# Display_SACA.net
KiCad netlist of a schematic drawn in Altium Designer
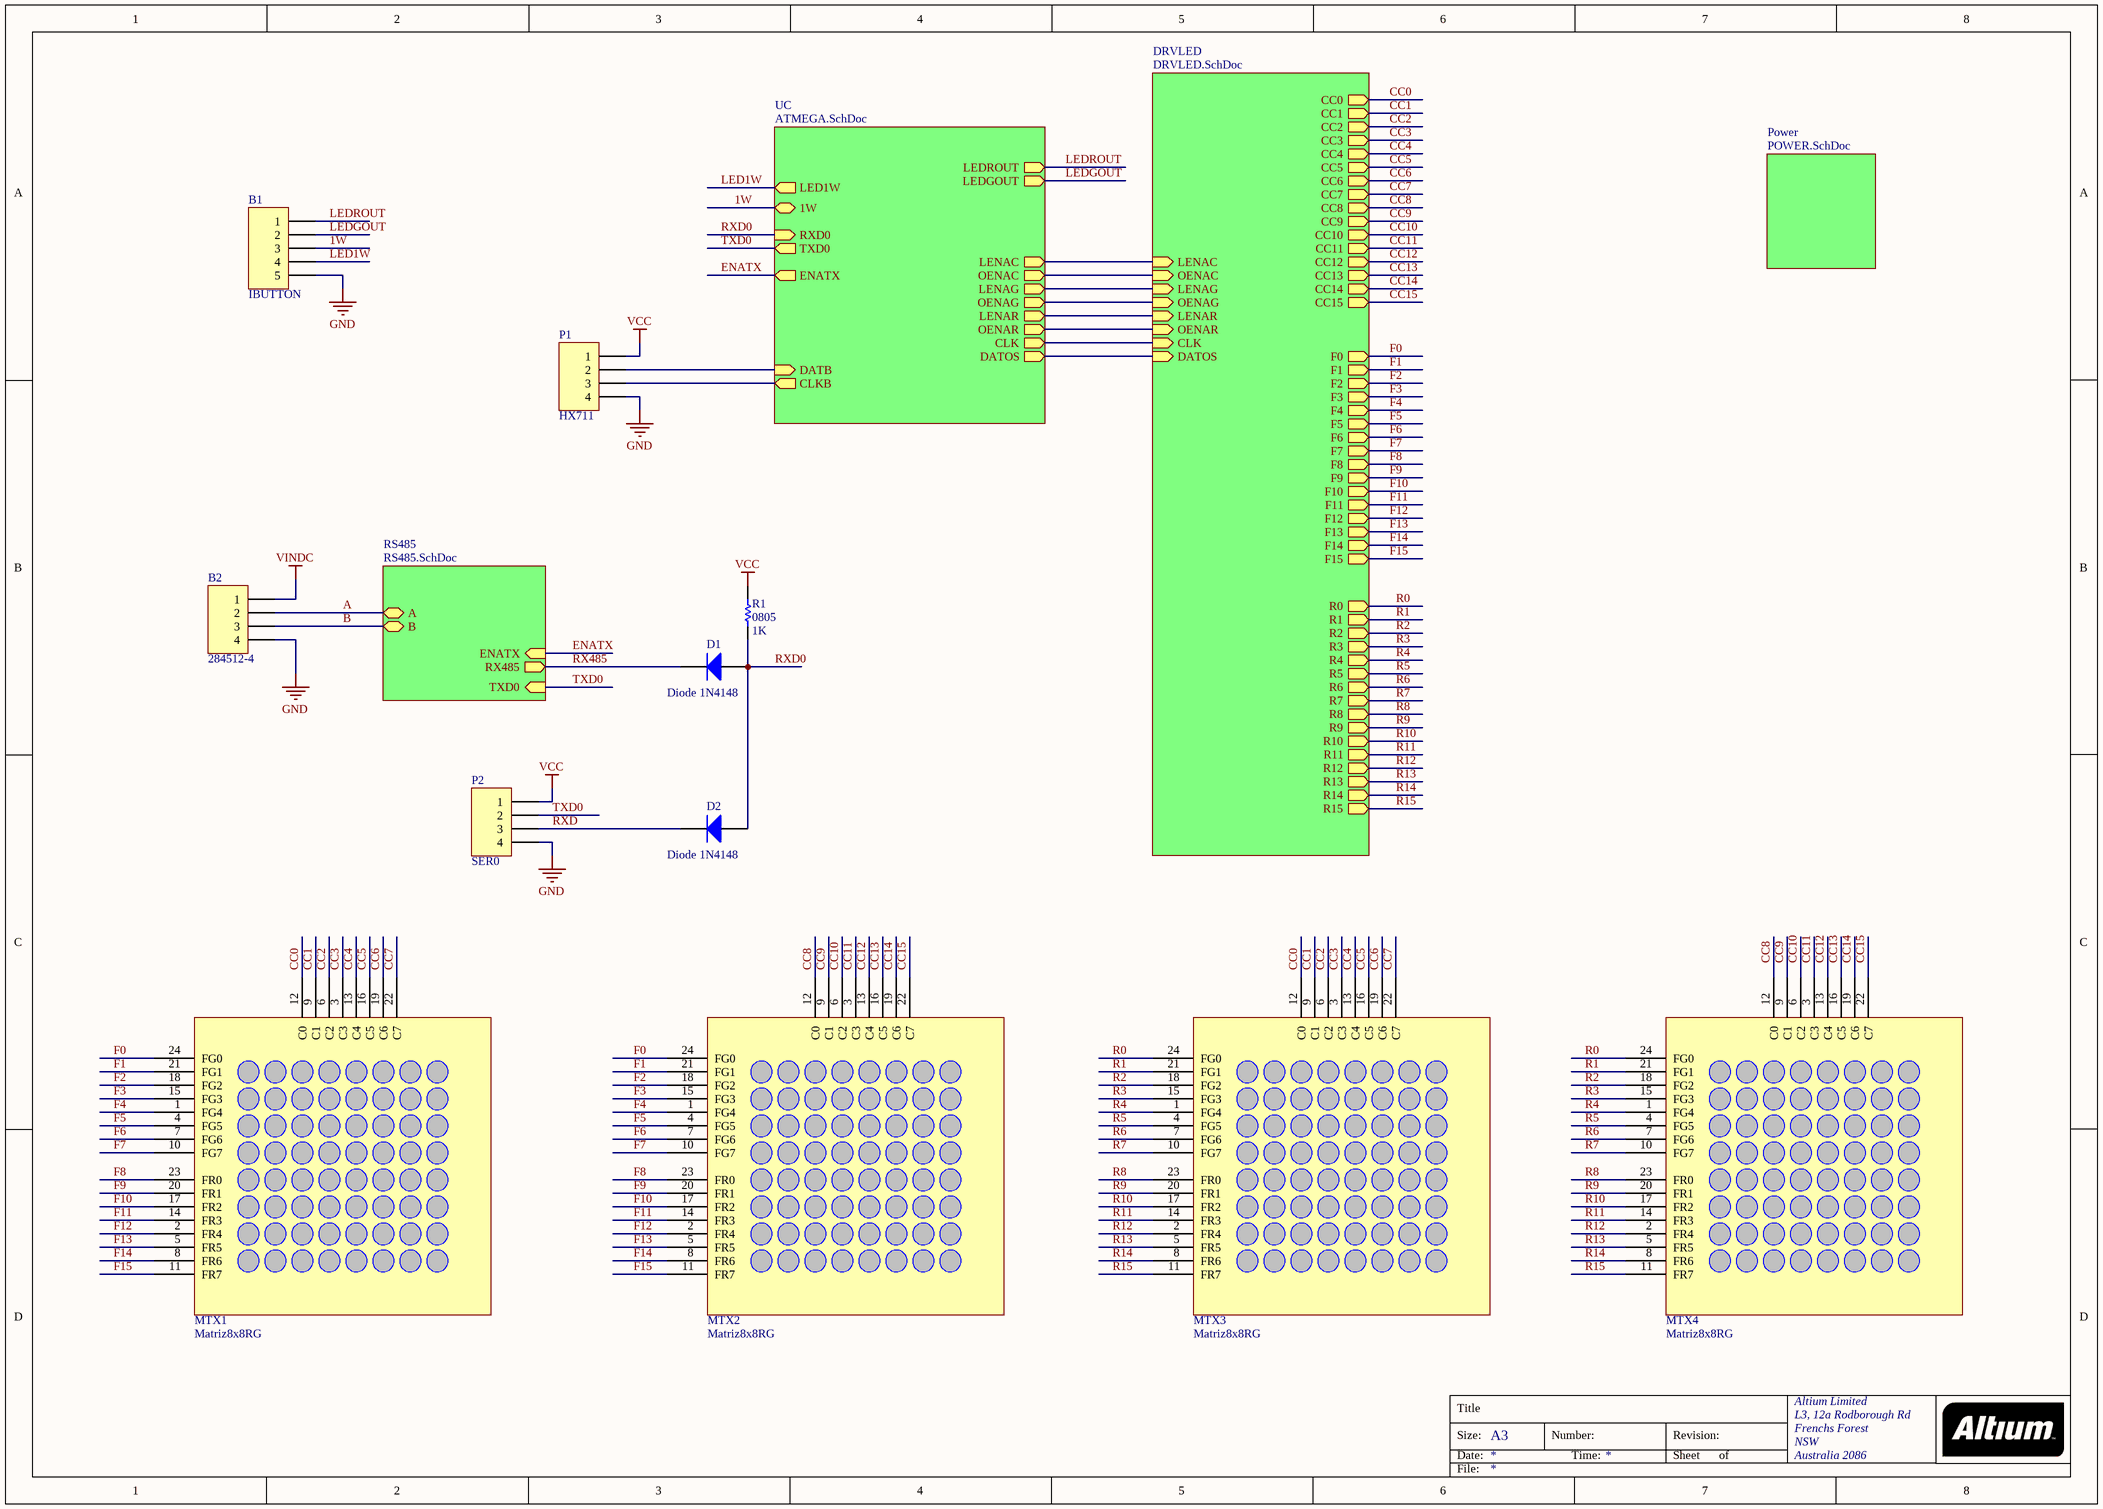
[diagram p0: Display_SACA.SchDoc]

(export (version "E")
  (design (tool "Eeschema 10.0.6"))
  (components
    (comp (ref "B1")
      (value "IBUTTON")
      (footprint "BORNERA5-3.5")
      (description "Header, 5-Pin")
      (fields (field (name "PART") "A98399-ND") (field (name "PUBLISHER") "Altium Limited"))
      (libsource (lib "PROPIASchlib") (part "Bornera 5 3.5mm"))
    )
    (comp (ref "B2")
      (value "284512-4")
      (footprint "BORNERA4-3.5")
      (description "TERM BLOCK HEADER  4POS R/A 3.5MM")
      (fields (field (name "PART") "A98398-ND") (field (name "PUBLISHER") "Altium Limited"))
      (libsource (lib "PROPIASchlib") (part "BORNERA4-3.5"))
    )
    (comp (ref "D1")
      (value "Diode 1N4148")
      (footprint "1N4148SMD")
      (description "1N4148")
      (fields (field (name "PART") "1N4148WTPMSCT") (field (name "PUBLISHER") "Altium Limited"))
      (libsource (lib "PROPIASchlib") (part "Diode 1N4148"))
    )
    (comp (ref "D2")
      (value "Diode 1N4148")
      (footprint "1N4148SMD")
      (description "1N4148")
      (fields (field (name "PART") "1N4148WTPMSCT") (field (name "PUBLISHER") "Altium Limited"))
      (libsource (lib "PROPIASchlib") (part "Diode 1N4148"))
    )
    (comp (ref "MTX1")
      (value "Matriz8x8RG")
      (footprint "MatrizFuturlec")
      (description "MATRIZ8X8 RG Anodo Comun Columnas")
      (libsource (lib "PROPIASchlib") (part "Matriz8x8RG"))
    )
    (comp (ref "MTX2")
      (value "Matriz8x8RG")
      (footprint "MatrizFuturlec")
      (description "MATRIZ8X8 RG Anodo Comun Columnas")
      (libsource (lib "PROPIASchlib") (part "Matriz8x8RG"))
    )
    (comp (ref "MTX3")
      (value "Matriz8x8RG")
      (footprint "MatrizFuturlec")
      (description "MATRIZ8X8 RG Anodo Comun Columnas")
      (libsource (lib "PROPIASchlib") (part "Matriz8x8RG"))
    )
    (comp (ref "MTX4")
      (value "Matriz8x8RG")
      (footprint "MatrizFuturlec")
      (description "MATRIZ8X8 RG Anodo Comun Columnas")
      (libsource (lib "PROPIASchlib") (part "Matriz8x8RG"))
    )
    (comp (ref "P1")
      (value "HX711")
      (footprint "HDR1X4")
      (description "Header, 4-Pin")
      (fields (field (name "PUBLISHER") "Altium Limited"))
      (libsource (lib "Miscellaneous Connectors") (part "Header 4"))
    )
    (comp (ref "P2")
      (value "SER0")
      (footprint "HDR1X4")
      (description "Header, 4-Pin")
      (fields (field (name "PUBLISHER") "Altium Limited"))
      (libsource (lib "Miscellaneous Connectors") (part "Header 4"))
    )
    (comp (ref "R1")
      (value "0805")
      (footprint "R0805")
      (description "Semiconductor Resistor")
      (fields
        (field (name "PART") "541-1.0KACT")
        (field (name "ALTIUM_VALUE") "1K")
        (field (name "PUBLISHER") "Altium Limited")
      )
      (libsource (lib "PROPIASchlib") (part "Res 0805 1K"))
    )
  )
  (nets
    (net (code "1") (name "/1W") (class "Default")
      (node (ref "B1") (pin "3") (pinfunction "3_3") (pintype "passive"))
    )
    (net (code "2") (name "/A") (class "Default")
      (node (ref "B2") (pin "2") (pinfunction "2_2") (pintype "passive"))
    )
    (net (code "3") (name "/B") (class "Default")
      (node (ref "B2") (pin "3") (pinfunction "3_3") (pintype "passive"))
    )
    (net (code "4") (name "/CC0") (class "Default")
      (node (ref "MTX1") (pin "12") (pinfunction "C0_12") (pintype "passive"))
      (node (ref "MTX3") (pin "12") (pinfunction "C0_12") (pintype "passive"))
    )
    (net (code "5") (name "/CC1") (class "Default")
      (node (ref "MTX1") (pin "9") (pinfunction "C1_9") (pintype "passive"))
      (node (ref "MTX3") (pin "9") (pinfunction "C1_9") (pintype "passive"))
    )
    (net (code "6") (name "/CC2") (class "Default")
      (node (ref "MTX1") (pin "6") (pinfunction "C2_6") (pintype "passive"))
      (node (ref "MTX3") (pin "6") (pinfunction "C2_6") (pintype "passive"))
    )
    (net (code "7") (name "/CC3") (class "Default")
      (node (ref "MTX1") (pin "3") (pinfunction "C3_3") (pintype "passive"))
      (node (ref "MTX3") (pin "3") (pinfunction "C3_3") (pintype "passive"))
    )
    (net (code "8") (name "/CC4") (class "Default")
      (node (ref "MTX1") (pin "13") (pinfunction "C4_13") (pintype "passive"))
      (node (ref "MTX3") (pin "13") (pinfunction "C4_13") (pintype "passive"))
    )
    (net (code "9") (name "/CC5") (class "Default")
      (node (ref "MTX1") (pin "16") (pinfunction "C5_16") (pintype "passive"))
      (node (ref "MTX3") (pin "16") (pinfunction "C5_16") (pintype "passive"))
    )
    (net (code "10") (name "/CC6") (class "Default")
      (node (ref "MTX1") (pin "19") (pinfunction "C6_19") (pintype "passive"))
      (node (ref "MTX3") (pin "19") (pinfunction "C6_19") (pintype "passive"))
    )
    (net (code "11") (name "/CC7") (class "Default")
      (node (ref "MTX1") (pin "22") (pinfunction "C7_22") (pintype "passive"))
      (node (ref "MTX3") (pin "22") (pinfunction "C7_22") (pintype "passive"))
    )
    (net (code "12") (name "/CC8") (class "Default")
      (node (ref "MTX2") (pin "12") (pinfunction "C0_12") (pintype "passive"))
      (node (ref "MTX4") (pin "12") (pinfunction "C0_12") (pintype "passive"))
    )
    (net (code "13") (name "/CC9") (class "Default")
      (node (ref "MTX2") (pin "9") (pinfunction "C1_9") (pintype "passive"))
      (node (ref "MTX4") (pin "9") (pinfunction "C1_9") (pintype "passive"))
    )
    (net (code "14") (name "/CC10") (class "Default")
      (node (ref "MTX2") (pin "6") (pinfunction "C2_6") (pintype "passive"))
      (node (ref "MTX4") (pin "6") (pinfunction "C2_6") (pintype "passive"))
    )
    (net (code "15") (name "/CC11") (class "Default")
      (node (ref "MTX2") (pin "3") (pinfunction "C3_3") (pintype "passive"))
      (node (ref "MTX4") (pin "3") (pinfunction "C3_3") (pintype "passive"))
    )
    (net (code "16") (name "/CC12") (class "Default")
      (node (ref "MTX2") (pin "13") (pinfunction "C4_13") (pintype "passive"))
      (node (ref "MTX4") (pin "13") (pinfunction "C4_13") (pintype "passive"))
    )
    (net (code "17") (name "/CC13") (class "Default")
      (node (ref "MTX2") (pin "16") (pinfunction "C5_16") (pintype "passive"))
      (node (ref "MTX4") (pin "16") (pinfunction "C5_16") (pintype "passive"))
    )
    (net (code "18") (name "/CC14") (class "Default")
      (node (ref "MTX2") (pin "19") (pinfunction "C6_19") (pintype "passive"))
      (node (ref "MTX4") (pin "19") (pinfunction "C6_19") (pintype "passive"))
    )
    (net (code "19") (name "/CC15") (class "Default")
      (node (ref "MTX2") (pin "22") (pinfunction "C7_22") (pintype "passive"))
      (node (ref "MTX4") (pin "22") (pinfunction "C7_22") (pintype "passive"))
    )
    (net (code "21") (name "/CLKB") (class "Default")
      (node (ref "P1") (pin "3") (pinfunction "3_3") (pintype "passive"))
    )
    (net (code "22") (name "/DATB") (class "Default")
      (node (ref "P1") (pin "2") (pinfunction "2_2") (pintype "passive"))
    )
    (net (code "25") (name "/F0") (class "Default")
      (node (ref "MTX1") (pin "24") (pinfunction "FG0_24") (pintype "passive"))
      (node (ref "MTX2") (pin "24") (pinfunction "FG0_24") (pintype "passive"))
    )
    (net (code "26") (name "/F1") (class "Default")
      (node (ref "MTX1") (pin "21") (pinfunction "FG1_21") (pintype "passive"))
      (node (ref "MTX2") (pin "21") (pinfunction "FG1_21") (pintype "passive"))
    )
    (net (code "27") (name "/F2") (class "Default")
      (node (ref "MTX1") (pin "18") (pinfunction "FG2_18") (pintype "passive"))
      (node (ref "MTX2") (pin "18") (pinfunction "FG2_18") (pintype "passive"))
    )
    (net (code "28") (name "/F3") (class "Default")
      (node (ref "MTX1") (pin "15") (pinfunction "FG3_15") (pintype "passive"))
      (node (ref "MTX2") (pin "15") (pinfunction "FG3_15") (pintype "passive"))
    )
    (net (code "29") (name "/F4") (class "Default")
      (node (ref "MTX1") (pin "1") (pinfunction "FG4_1") (pintype "passive"))
      (node (ref "MTX2") (pin "1") (pinfunction "FG4_1") (pintype "passive"))
    )
    (net (code "30") (name "/F5") (class "Default")
      (node (ref "MTX1") (pin "4") (pinfunction "FG5_4") (pintype "passive"))
      (node (ref "MTX2") (pin "4") (pinfunction "FG5_4") (pintype "passive"))
    )
    (net (code "31") (name "/F6") (class "Default")
      (node (ref "MTX1") (pin "7") (pinfunction "FG6_7") (pintype "passive"))
      (node (ref "MTX2") (pin "7") (pinfunction "FG6_7") (pintype "passive"))
    )
    (net (code "32") (name "/F7") (class "Default")
      (node (ref "MTX1") (pin "10") (pinfunction "FG7_10") (pintype "passive"))
      (node (ref "MTX2") (pin "10") (pinfunction "FG7_10") (pintype "passive"))
    )
    (net (code "33") (name "/F8") (class "Default")
      (node (ref "MTX1") (pin "23") (pinfunction "FR0_23") (pintype "passive"))
      (node (ref "MTX2") (pin "23") (pinfunction "FR0_23") (pintype "passive"))
    )
    (net (code "34") (name "/F9") (class "Default")
      (node (ref "MTX1") (pin "20") (pinfunction "FR1_20") (pintype "passive"))
      (node (ref "MTX2") (pin "20") (pinfunction "FR1_20") (pintype "passive"))
    )
    (net (code "35") (name "/F10") (class "Default")
      (node (ref "MTX1") (pin "17") (pinfunction "FR2_17") (pintype "passive"))
      (node (ref "MTX2") (pin "17") (pinfunction "FR2_17") (pintype "passive"))
    )
    (net (code "36") (name "/F11") (class "Default")
      (node (ref "MTX1") (pin "14") (pinfunction "FR3_14") (pintype "passive"))
      (node (ref "MTX2") (pin "14") (pinfunction "FR3_14") (pintype "passive"))
    )
    (net (code "37") (name "/F12") (class "Default")
      (node (ref "MTX1") (pin "2") (pinfunction "FR4_2") (pintype "passive"))
      (node (ref "MTX2") (pin "2") (pinfunction "FR4_2") (pintype "passive"))
    )
    (net (code "38") (name "/F13") (class "Default")
      (node (ref "MTX1") (pin "5") (pinfunction "FR5_5") (pintype "passive"))
      (node (ref "MTX2") (pin "5") (pinfunction "FR5_5") (pintype "passive"))
    )
    (net (code "39") (name "/F14") (class "Default")
      (node (ref "MTX1") (pin "8") (pinfunction "FR6_8") (pintype "passive"))
      (node (ref "MTX2") (pin "8") (pinfunction "FR6_8") (pintype "passive"))
    )
    (net (code "40") (name "/F15") (class "Default")
      (node (ref "MTX1") (pin "11") (pinfunction "FR7_11") (pintype "passive"))
      (node (ref "MTX2") (pin "11") (pinfunction "FR7_11") (pintype "passive"))
    )
    (net (code "41") (name "/LED1W") (class "Default")
      (node (ref "B1") (pin "4") (pinfunction "4_4") (pintype "passive"))
    )
    (net (code "42") (name "/LEDGOUT") (class "Default")
      (node (ref "B1") (pin "2") (pinfunction "2_2") (pintype "passive"))
    )
    (net (code "43") (name "/LEDROUT") (class "Default")
      (node (ref "B1") (pin "1") (pinfunction "1_1") (pintype "passive"))
    )
    (net (code "50") (name "/R0") (class "Default")
      (node (ref "MTX3") (pin "24") (pinfunction "FG0_24") (pintype "passive"))
      (node (ref "MTX4") (pin "24") (pinfunction "FG0_24") (pintype "passive"))
    )
    (net (code "51") (name "/R1") (class "Default")
      (node (ref "MTX3") (pin "21") (pinfunction "FG1_21") (pintype "passive"))
      (node (ref "MTX4") (pin "21") (pinfunction "FG1_21") (pintype "passive"))
    )
    (net (code "52") (name "/R2") (class "Default")
      (node (ref "MTX3") (pin "18") (pinfunction "FG2_18") (pintype "passive"))
      (node (ref "MTX4") (pin "18") (pinfunction "FG2_18") (pintype "passive"))
    )
    (net (code "53") (name "/R3") (class "Default")
      (node (ref "MTX3") (pin "15") (pinfunction "FG3_15") (pintype "passive"))
      (node (ref "MTX4") (pin "15") (pinfunction "FG3_15") (pintype "passive"))
    )
    (net (code "54") (name "/R4") (class "Default")
      (node (ref "MTX3") (pin "1") (pinfunction "FG4_1") (pintype "passive"))
      (node (ref "MTX4") (pin "1") (pinfunction "FG4_1") (pintype "passive"))
    )
    (net (code "55") (name "/R5") (class "Default")
      (node (ref "MTX3") (pin "4") (pinfunction "FG5_4") (pintype "passive"))
      (node (ref "MTX4") (pin "4") (pinfunction "FG5_4") (pintype "passive"))
    )
    (net (code "56") (name "/R6") (class "Default")
      (node (ref "MTX3") (pin "7") (pinfunction "FG6_7") (pintype "passive"))
      (node (ref "MTX4") (pin "7") (pinfunction "FG6_7") (pintype "passive"))
    )
    (net (code "57") (name "/R7") (class "Default")
      (node (ref "MTX3") (pin "10") (pinfunction "FG7_10") (pintype "passive"))
      (node (ref "MTX4") (pin "10") (pinfunction "FG7_10") (pintype "passive"))
    )
    (net (code "58") (name "/R8") (class "Default")
      (node (ref "MTX3") (pin "23") (pinfunction "FR0_23") (pintype "passive"))
      (node (ref "MTX4") (pin "23") (pinfunction "FR0_23") (pintype "passive"))
    )
    (net (code "59") (name "/R9") (class "Default")
      (node (ref "MTX3") (pin "20") (pinfunction "FR1_20") (pintype "passive"))
      (node (ref "MTX4") (pin "20") (pinfunction "FR1_20") (pintype "passive"))
    )
    (net (code "60") (name "/R10") (class "Default")
      (node (ref "MTX3") (pin "17") (pinfunction "FR2_17") (pintype "passive"))
      (node (ref "MTX4") (pin "17") (pinfunction "FR2_17") (pintype "passive"))
    )
    (net (code "61") (name "/R11") (class "Default")
      (node (ref "MTX3") (pin "14") (pinfunction "FR3_14") (pintype "passive"))
      (node (ref "MTX4") (pin "14") (pinfunction "FR3_14") (pintype "passive"))
    )
    (net (code "62") (name "/R12") (class "Default")
      (node (ref "MTX3") (pin "2") (pinfunction "FR4_2") (pintype "passive"))
      (node (ref "MTX4") (pin "2") (pinfunction "FR4_2") (pintype "passive"))
    )
    (net (code "63") (name "/R13") (class "Default")
      (node (ref "MTX3") (pin "5") (pinfunction "FR5_5") (pintype "passive"))
      (node (ref "MTX4") (pin "5") (pinfunction "FR5_5") (pintype "passive"))
    )
    (net (code "64") (name "/R14") (class "Default")
      (node (ref "MTX3") (pin "8") (pinfunction "FR6_8") (pintype "passive"))
      (node (ref "MTX4") (pin "8") (pinfunction "FR6_8") (pintype "passive"))
    )
    (net (code "65") (name "/R15") (class "Default")
      (node (ref "MTX3") (pin "11") (pinfunction "FR7_11") (pintype "passive"))
      (node (ref "MTX4") (pin "11") (pinfunction "FR7_11") (pintype "passive"))
    )
    (net (code "66") (name "/RX485") (class "Default")
      (node (ref "D1") (pin "2") (pinfunction "K_2") (pintype "passive"))
    )
    (net (code "67") (name "/RXD") (class "Default")
      (node (ref "D2") (pin "2") (pinfunction "K_2") (pintype "passive"))
      (node (ref "P2") (pin "3") (pinfunction "3_3") (pintype "passive"))
    )
    (net (code "68") (name "/RXD0") (class "Default")
      (node (ref "D1") (pin "1") (pinfunction "A_1") (pintype "passive"))
      (node (ref "D2") (pin "1") (pinfunction "A_1") (pintype "passive"))
      (node (ref "R1") (pin "1") (pinfunction "1_1") (pintype "passive"))
    )
    (net (code "69") (name "/TXD0") (class "Default")
      (node (ref "P2") (pin "2") (pinfunction "2_2") (pintype "passive"))
    )
    (net (code "70") (name "GND") (class "Default")
      (node (ref "B1") (pin "5") (pinfunction "5_5") (pintype "passive"))
      (node (ref "B2") (pin "4") (pinfunction "4_4") (pintype "passive"))
      (node (ref "P1") (pin "4") (pinfunction "4_4") (pintype "passive"))
      (node (ref "P2") (pin "4") (pinfunction "4_4") (pintype "passive"))
    )
    (net (code "71") (name "VCC") (class "Default")
      (node (ref "P1") (pin "1") (pinfunction "1_1") (pintype "passive"))
      (node (ref "P2") (pin "1") (pinfunction "1_1") (pintype "passive"))
      (node (ref "R1") (pin "2") (pinfunction "2_2") (pintype "passive"))
    )
    (net (code "72") (name "VINDC") (class "Default")
      (node (ref "B2") (pin "1") (pinfunction "1_1") (pintype "passive"))
    )
  )
)
